# HealthMonitor.net
KiCad netlist of a schematic drawn in EAGLE
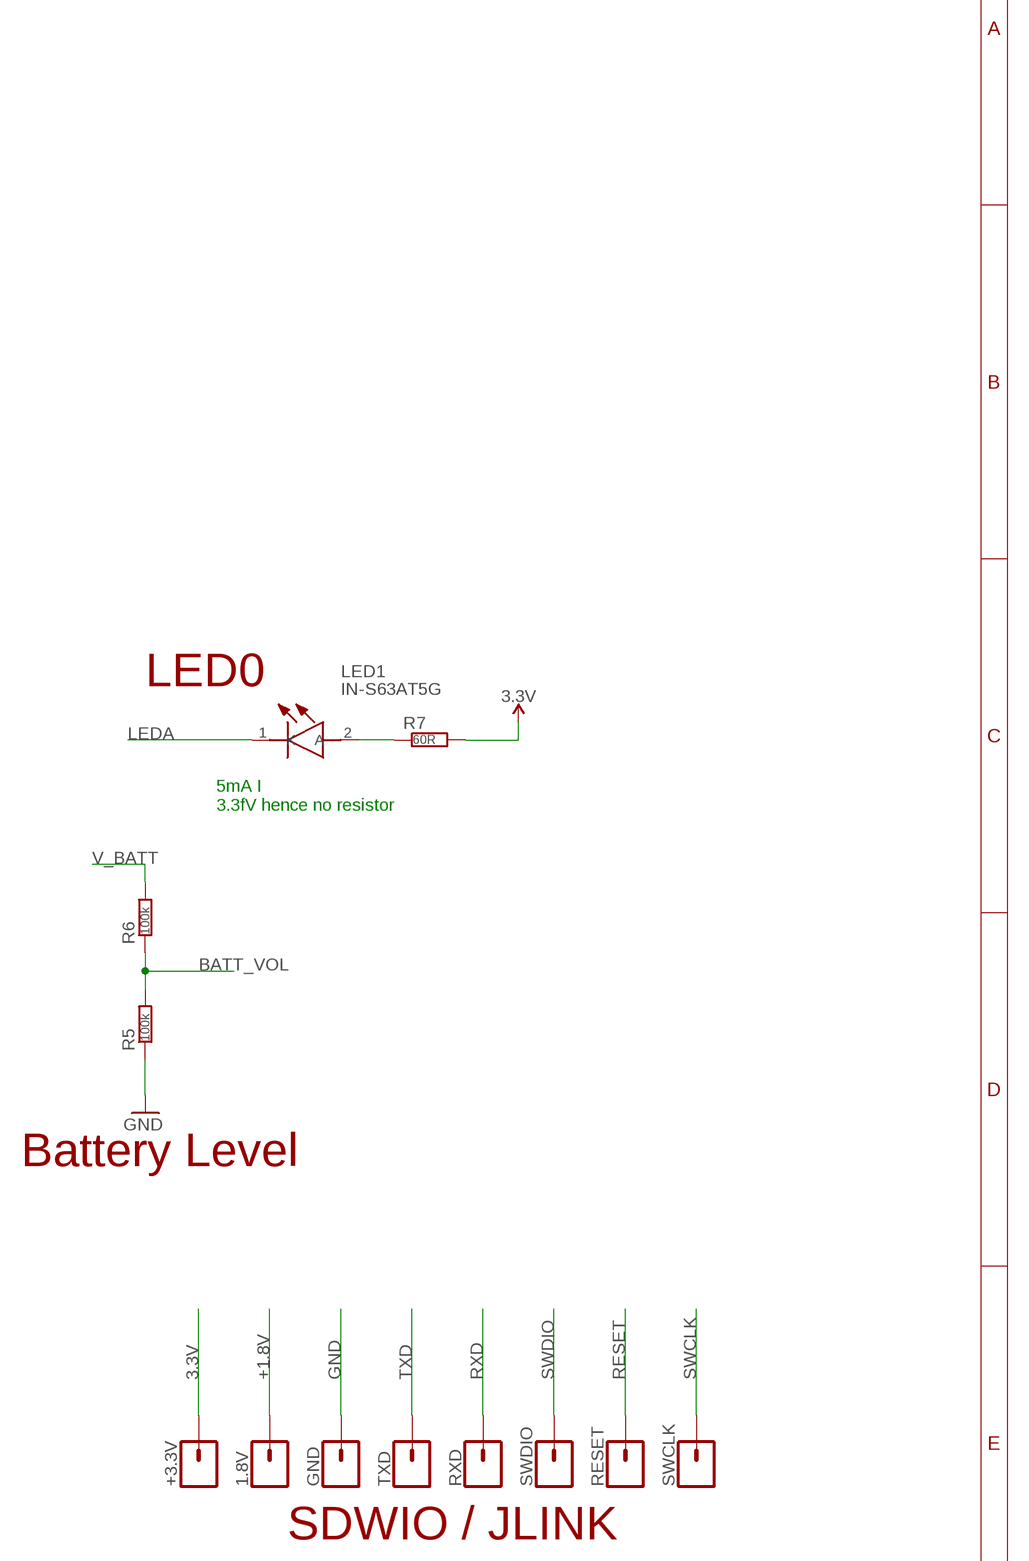
[diagram p0: schematic, sheet 1, part 1 of 2]
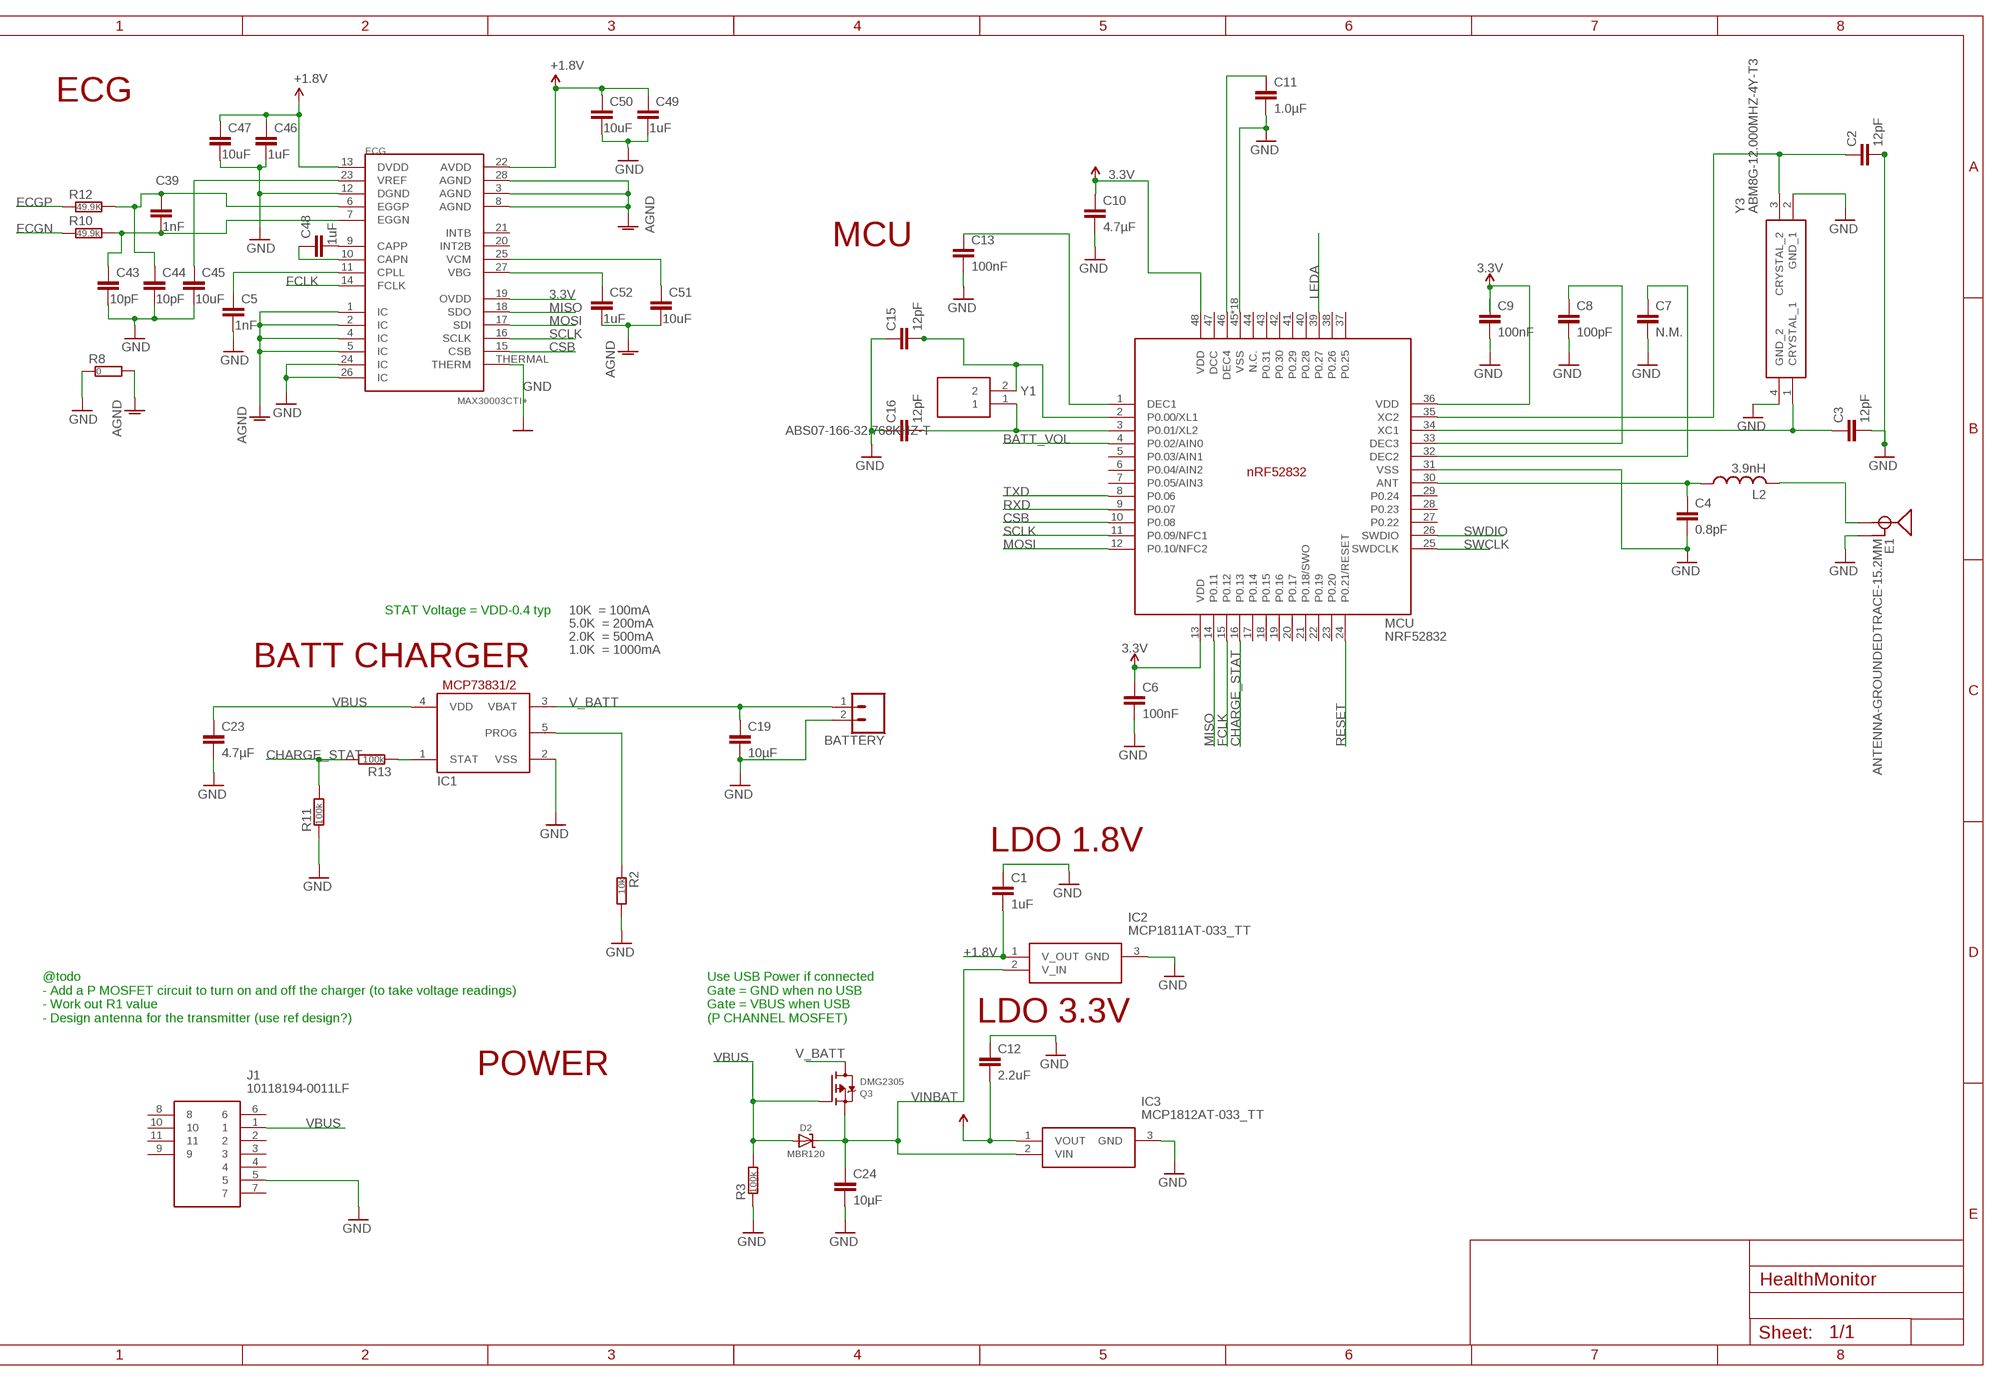
[diagram p1: schematic, sheet 1, part 2 of 2]

(export (version "E")
  (design (tool "Eeschema 10.0.6"))
  (components
    (comp (ref "+3.3V")
      (value "CONN_01")
      (footprint "eagle-import:1X01")
      (libsource (lib "eagle-import") (part "CONN_01"))
    )
    (comp (ref "1.8V")
      (value "CONN_01")
      (footprint "eagle-import:1X01")
      (libsource (lib "eagle-import") (part "CONN_01"))
    )
    (comp (ref "BATTERY")
      (value "CONN_02")
      (footprint "eagle-import:1X02")
      (libsource (lib "eagle-import") (part "CONN_02"))
    )
    (comp (ref "C1")
      (value "1uF")
      (footprint "eagle-import:RESC0603_N")
      (libsource (lib "eagle-import") (part "CAPACITOR_0603_N"))
    )
    (comp (ref "C2")
      (value "12pF")
      (footprint "eagle-import:RESC0603_N")
      (libsource (lib "eagle-import") (part "CAPACITOR_0603_N"))
    )
    (comp (ref "C3")
      (value "12pF")
      (footprint "eagle-import:RESC0603_N")
      (libsource (lib "eagle-import") (part "CAPACITOR_0603_N"))
    )
    (comp (ref "C4")
      (value "0.8pF")
      (footprint "eagle-import:RESC0603_N")
      (libsource (lib "eagle-import") (part "CAPACITOR_0603_N"))
    )
    (comp (ref "C5")
      (value "1nF")
      (footprint "eagle-import:RESC0603_N")
      (libsource (lib "eagle-import") (part "CAPACITOR_0603_N"))
    )
    (comp (ref "C6")
      (value "100nF")
      (footprint "eagle-import:RESC0603_N")
      (libsource (lib "eagle-import") (part "CAPACITOR_0603_N"))
    )
    (comp (ref "C7")
      (value "N.M.")
      (footprint "eagle-import:RESC0603_N")
      (libsource (lib "eagle-import") (part "CAPACITOR_0603_N"))
    )
    (comp (ref "C8")
      (value "100pF")
      (footprint "eagle-import:RESC0603_N")
      (libsource (lib "eagle-import") (part "CAPACITOR_0603_N"))
    )
    (comp (ref "C9")
      (value "100nF")
      (footprint "eagle-import:RESC0603_N")
      (libsource (lib "eagle-import") (part "CAPACITOR_0603_N"))
    )
    (comp (ref "C10")
      (value "4.7µF")
      (footprint "eagle-import:RESC0603_N")
      (libsource (lib "eagle-import") (part "CAPACITOR_0603_N"))
    )
    (comp (ref "C11")
      (value "1.0µF")
      (footprint "eagle-import:RESC0603_N")
      (libsource (lib "eagle-import") (part "CAPACITOR_0603_N"))
    )
    (comp (ref "C12")
      (value "2.2uF")
      (footprint "eagle-import:RESC0603_N")
      (libsource (lib "eagle-import") (part "CAPACITOR_0603_N"))
    )
    (comp (ref "C13")
      (value "100nF")
      (footprint "eagle-import:RESC0603_N")
      (libsource (lib "eagle-import") (part "CAPACITOR_0603_N"))
    )
    (comp (ref "C15")
      (value "12pF")
      (footprint "eagle-import:RESC0603_N")
      (libsource (lib "eagle-import") (part "CAPACITOR_0603_N"))
    )
    (comp (ref "C16")
      (value "12pF")
      (footprint "eagle-import:RESC0603_N")
      (libsource (lib "eagle-import") (part "CAPACITOR_0603_N"))
    )
    (comp (ref "C19")
      (value "10µF")
      (footprint "eagle-import:RESC0603_N")
      (libsource (lib "eagle-import") (part "CAPACITOR_0603_N"))
    )
    (comp (ref "C23")
      (value "4.7µF")
      (footprint "eagle-import:RESC0603_N")
      (libsource (lib "eagle-import") (part "CAPACITOR_0603_N"))
    )
    (comp (ref "C24")
      (value "10µF")
      (footprint "eagle-import:RESC0603_N")
      (libsource (lib "eagle-import") (part "CAPACITOR_0603_N"))
    )
    (comp (ref "C39")
      (value "1nF")
      (footprint "eagle-import:RESC0603_N")
      (libsource (lib "eagle-import") (part "CAPACITOR_0603_N"))
    )
    (comp (ref "C43")
      (value "10pF")
      (footprint "eagle-import:RESC0603_N")
      (libsource (lib "eagle-import") (part "CAPACITOR_0603_N"))
    )
    (comp (ref "C44")
      (value "10pF")
      (footprint "eagle-import:RESC0603_N")
      (libsource (lib "eagle-import") (part "CAPACITOR_0603_N"))
    )
    (comp (ref "C45")
      (value "10uF")
      (footprint "eagle-import:RESC0603_N")
      (libsource (lib "eagle-import") (part "CAPACITOR_0603_N"))
    )
    (comp (ref "C46")
      (value "1uF")
      (footprint "eagle-import:RESC0603_N")
      (libsource (lib "eagle-import") (part "CAPACITOR_0603_N"))
    )
    (comp (ref "C47")
      (value "10uF")
      (footprint "eagle-import:RESC0603_N")
      (libsource (lib "eagle-import") (part "CAPACITOR_0603_N"))
    )
    (comp (ref "C48")
      (value "1uF")
      (footprint "eagle-import:RESC0603_N")
      (libsource (lib "eagle-import") (part "CAPACITOR_0603_N"))
    )
    (comp (ref "C49")
      (value "1uF")
      (footprint "eagle-import:RESC0603_N")
      (libsource (lib "eagle-import") (part "CAPACITOR_0603_N"))
    )
    (comp (ref "C50")
      (value "10uF")
      (footprint "eagle-import:RESC0603_N")
      (libsource (lib "eagle-import") (part "CAPACITOR_0603_N"))
    )
    (comp (ref "C51")
      (value "10uF")
      (footprint "eagle-import:RESC0603_N")
      (libsource (lib "eagle-import") (part "CAPACITOR_0603_N"))
    )
    (comp (ref "C52")
      (value "1uF")
      (footprint "eagle-import:RESC0603_N")
      (libsource (lib "eagle-import") (part "CAPACITOR_0603_N"))
    )
    (comp (ref "D2")
      (value "MBR120")
      (footprint "eagle-import:SOD-123")
      (libsource (lib "eagle-import") (part "DIODE-SCHOTTKYSOD-123"))
    )
    (comp (ref "E1")
      (value "ANTENNA-GROUNDEDTRACE-15.2MM")
      (footprint "eagle-import:TRACE_ANTENNA_2.4GHZ_15.2MM")
      (libsource (lib "eagle-import") (part "ANTENNA-GROUNDEDTRACE-15.2MM"))
    )
    (comp (ref "ECG")
      (value "MAX30003CTI+")
      (footprint "eagle-import:QFN-28")
      (libsource (lib "eagle-import") (part "MAX30003"))
    )
    (comp (ref "GND")
      (value "CONN_01")
      (footprint "eagle-import:1X01")
      (libsource (lib "eagle-import") (part "CONN_01"))
    )
    (comp (ref "IC1")
      (value "MCP73831/OT")
      (footprint "eagle-import:SOT23-5L")
      (libsource (lib "eagle-import") (part "MCP73831/OT"))
    )
    (comp (ref "IC2")
      (value "MCP1811AT-033_TT")
      (footprint "eagle-import:SOT95P237X112-3N@1")
      (fields
        (field (name "MANUFACTURER_PART_NUMBER") "MCP1811AT-033/TT")
        (field (name "MOUSER_PART_NUMBER") "579-MCP1811AT-033/TT")
      )
      (libsource (lib "eagle-import") (part "MCP1811AT-033_TT"))
    )
    (comp (ref "IC3")
      (value "MCP1812AT-033_TT")
      (footprint "eagle-import:SOT95P237X112-3N")
      (fields
        (field (name "MANUFACTURER_PART_NUMBER") "MCP1812AT-033/TT")
        (field (name "MOUSER_PART_NUMBER") "579-MCP1812AT-033/TT")
      )
      (libsource (lib "eagle-import") (part "MCP1812AT-033_TT"))
    )
    (comp (ref "J1")
      (value "10118194-0011LF")
      (footprint "eagle-import:101181940011LF")
      (fields (field (name "MOUSER_PART_NUMBER") "649-10118194-0011LF"))
      (libsource (lib "eagle-import") (part "10118194-0011LF"))
    )
    (comp (ref "L2")
      (value "3.9nH")
      (footprint "eagle-import:RESC0603_N")
      (libsource (lib "eagle-import") (part "INDUCTOR_0603_N"))
    )
    (comp (ref "LED1")
      (value "IN-S63AT5G")
      (footprint "eagle-import:LEDM168X39N")
      (fields (field (name "MOUSER_PART_NUMBER") "743-IN-S63AT5G"))
      (libsource (lib "eagle-import") (part "IN-S63AT5G"))
    )
    (comp (ref "MCU")
      (value "NRF52832")
      (footprint "eagle-import:QFN40P600X600X90-48_N")
      (libsource (lib "eagle-import") (part "NRF52832"))
    )
    (comp (ref "Q3")
      (value "DMG2305")
      (footprint "eagle-import:SOT23-R")
      (libsource (lib "eagle-import") (part "MOSFET-P"))
    )
    (comp (ref "R2")
      (value "10k")
      (footprint "eagle-import:RESC0603_N")
      (libsource (lib "eagle-import") (part "RESISTOR_0603_N"))
    )
    (comp (ref "R3")
      (value "100k")
      (footprint "eagle-import:RESC0603_N")
      (libsource (lib "eagle-import") (part "RESISTOR_0603_N"))
    )
    (comp (ref "R5")
      (value "100k")
      (footprint "eagle-import:RESC0603_N")
      (libsource (lib "eagle-import") (part "RESISTOR_0603_N"))
    )
    (comp (ref "R6")
      (value "100k")
      (footprint "eagle-import:RESC0603_N")
      (libsource (lib "eagle-import") (part "RESISTOR_0603_N"))
    )
    (comp (ref "R7")
      (value "60R")
      (footprint "eagle-import:RESC0603_N")
      (libsource (lib "eagle-import") (part "RESISTOR_0603_N"))
    )
    (comp (ref "R8")
      (value "0")
      (footprint "eagle-import:RESC0603_N")
      (libsource (lib "eagle-import") (part "RESISTOR_0603_N"))
    )
    (comp (ref "R10")
      (value "49.9k")
      (footprint "eagle-import:RESC0603_N")
      (libsource (lib "eagle-import") (part "RESISTOR_0603_N"))
    )
    (comp (ref "R11")
      (value "100k")
      (footprint "eagle-import:RESC0603_N")
      (libsource (lib "eagle-import") (part "RESISTOR_0603_N"))
    )
    (comp (ref "R12")
      (value "49.9K")
      (footprint "eagle-import:RESC0603_N")
      (libsource (lib "eagle-import") (part "RESISTOR_0603_N"))
    )
    (comp (ref "R13")
      (value "100k")
      (footprint "eagle-import:RESC0603_N")
      (libsource (lib "eagle-import") (part "RESISTOR_0603_N"))
    )
    (comp (ref "RESET")
      (value "CONN_01")
      (footprint "eagle-import:1X01")
      (libsource (lib "eagle-import") (part "CONN_01"))
    )
    (comp (ref "RXD")
      (value "CONN_01")
      (footprint "eagle-import:1X01")
      (libsource (lib "eagle-import") (part "CONN_01"))
    )
    (comp (ref "SWCLK")
      (value "CONN_01")
      (footprint "eagle-import:1X01")
      (libsource (lib "eagle-import") (part "CONN_01"))
    )
    (comp (ref "SWDIO")
      (value "CONN_01")
      (footprint "eagle-import:1X01")
      (libsource (lib "eagle-import") (part "CONN_01"))
    )
    (comp (ref "TXD")
      (value "CONN_01")
      (footprint "eagle-import:1X01")
      (libsource (lib "eagle-import") (part "CONN_01"))
    )
    (comp (ref "Y1")
      (value "ABS07-166-32.768KHZ-T")
      (footprint "eagle-import:ABS0716632768KHZT")
      (fields
        (field (name "MOUSER_PART_NUMBER") "815-ABS0716632.768KT")
        (field (name "RS_PART_NUMBER") "1753474P")
      )
      (libsource (lib "eagle-import") (part "ABS07-166-32.768KHZ-T"))
    )
    (comp (ref "Y3")
      (value "ABM8G-12.000MHZ-4Y-T3")
      (footprint "eagle-import:ABM8G16000MHZB4YT")
      (fields
        (field (name "MOUSER_PART_NUMBER") "815-ABM8G-12-4YT3")
        (field (name "RS_PART_NUMBER") "1712832P")
      )
      (libsource (lib "eagle-import") (part "ABM8G-12.000MHZ-4Y-T3"))
    )
  )
  (nets
    (net (code "1") (name "+1.8V") (class "Default")
      (node (ref "1.8V") (pin "1") (pinfunction "1_1") (pintype "passive"))
      (node (ref "C1") (pin "2") (pinfunction "2_2") (pintype "passive"))
      (node (ref "C46") (pin "1") (pinfunction "1_1") (pintype "passive"))
      (node (ref "C47") (pin "1") (pinfunction "1_1") (pintype "passive"))
      (node (ref "C49") (pin "1") (pinfunction "1_1") (pintype "passive"))
      (node (ref "C50") (pin "1") (pinfunction "1_1") (pintype "passive"))
      (node (ref "ECG") (pin "13") (pinfunction "DVDD_13") (pintype "bidirectional"))
      (node (ref "ECG") (pin "22") (pinfunction "AVDD_22") (pintype "bidirectional"))
      (node (ref "IC2") (pin "1") (pinfunction "V_OUT_1") (pintype "bidirectional"))
    )
    (net (code "2") (name "/BATT_VOL") (class "Default")
      (node (ref "MCU") (pin "4") (pinfunction "P0.02/AIN0_4") (pintype "bidirectional"))
      (node (ref "R5") (pin "2") (pinfunction "2_2") (pintype "passive"))
      (node (ref "R6") (pin "1") (pinfunction "1_1") (pintype "passive"))
    )
    (net (code "3") (name "/CHARGE_STAT") (class "Default")
      (node (ref "MCU") (pin "16") (pinfunction "P0.13_16") (pintype "bidirectional"))
      (node (ref "R11") (pin "2") (pinfunction "2_2") (pintype "passive"))
      (node (ref "R13") (pin "2") (pinfunction "2_2") (pintype "passive"))
    )
    (net (code "4") (name "/CSB") (class "Default")
      (node (ref "ECG") (pin "15") (pinfunction "CSB_15") (pintype "bidirectional"))
      (node (ref "MCU") (pin "10") (pinfunction "P0.08_10") (pintype "bidirectional"))
    )
    (net (code "5") (name "/ECGN") (class "Default")
      (node (ref "R10") (pin "1") (pinfunction "1_1") (pintype "passive"))
    )
    (net (code "6") (name "/ECGP") (class "Default")
      (node (ref "R12") (pin "1") (pinfunction "1_1") (pintype "passive"))
    )
    (net (code "7") (name "/FCLK") (class "Default")
      (node (ref "ECG") (pin "14") (pinfunction "FCLK_14") (pintype "bidirectional"))
      (node (ref "MCU") (pin "15") (pinfunction "P0.12_15") (pintype "bidirectional"))
    )
    (net (code "8") (name "/LEDA") (class "Default")
      (node (ref "LED1") (pin "1") (pinfunction "K_1") (pintype "bidirectional"))
      (node (ref "MCU") (pin "39") (pinfunction "P0.27_39") (pintype "bidirectional"))
    )
    (net (code "9") (name "/MISO") (class "Default")
      (node (ref "ECG") (pin "18") (pinfunction "SDO_18") (pintype "bidirectional"))
      (node (ref "MCU") (pin "14") (pinfunction "P0.11_14") (pintype "bidirectional"))
    )
    (net (code "10") (name "/MOSI") (class "Default")
      (node (ref "ECG") (pin "17") (pinfunction "SDI_17") (pintype "bidirectional"))
      (node (ref "MCU") (pin "12") (pinfunction "P0.10/NFC2_12") (pintype "bidirectional"))
    )
    (net (code "11") (name "/RESET") (class "Default")
      (node (ref "MCU") (pin "24") (pinfunction "P0.21/RESET_24") (pintype "bidirectional"))
      (node (ref "RESET") (pin "1") (pinfunction "1_1") (pintype "passive"))
    )
    (net (code "12") (name "/RXD") (class "Default")
      (node (ref "MCU") (pin "9") (pinfunction "P0.07_9") (pintype "bidirectional"))
      (node (ref "RXD") (pin "1") (pinfunction "1_1") (pintype "passive"))
    )
    (net (code "13") (name "/SCLK") (class "Default")
      (node (ref "ECG") (pin "16") (pinfunction "SCLK_16") (pintype "bidirectional"))
      (node (ref "MCU") (pin "11") (pinfunction "P0.09/NFC1_11") (pintype "bidirectional"))
    )
    (net (code "14") (name "/SWCLK") (class "Default")
      (node (ref "MCU") (pin "25") (pinfunction "SWDCLK_25") (pintype "input"))
      (node (ref "SWCLK") (pin "1") (pinfunction "1_1") (pintype "passive"))
    )
    (net (code "15") (name "/SWDIO") (class "Default")
      (node (ref "MCU") (pin "26") (pinfunction "SWDIO_26") (pintype "bidirectional"))
      (node (ref "SWDIO") (pin "1") (pinfunction "1_1") (pintype "passive"))
    )
    (net (code "16") (name "/TXD") (class "Default")
      (node (ref "MCU") (pin "8") (pinfunction "P0.06_8") (pintype "bidirectional"))
      (node (ref "TXD") (pin "1") (pinfunction "1_1") (pintype "passive"))
    )
    (net (code "17") (name "/VBUS") (class "Default")
      (node (ref "C23") (pin "1") (pinfunction "1_1") (pintype "passive"))
      (node (ref "D2") (pin "A") (pinfunction "A_A") (pintype "passive"))
      (node (ref "IC1") (pin "4") (pinfunction "VDD_4") (pintype "power_in"))
      (node (ref "J1") (pin "1") (pinfunction "1_1") (pintype "bidirectional"))
      (node (ref "Q3") (pin "1") (pinfunction "G_1") (pintype "passive"))
      (node (ref "R3") (pin "2") (pinfunction "2_2") (pintype "passive"))
    )
    (net (code "18") (name "/VINBAT") (class "Default")
      (node (ref "C24") (pin "1") (pinfunction "1_1") (pintype "passive"))
      (node (ref "D2") (pin "C") (pinfunction "C_C") (pintype "passive"))
      (node (ref "IC2") (pin "2") (pinfunction "V_IN_2") (pintype "bidirectional"))
      (node (ref "IC3") (pin "2") (pinfunction "VIN_2") (pintype "bidirectional"))
      (node (ref "Q3") (pin "2") (pinfunction "S_2") (pintype "passive"))
    )
    (net (code "19") (name "/V_BATT") (class "Default")
      (node (ref "BATTERY") (pin "1") (pinfunction "1_1") (pintype "passive"))
      (node (ref "C19") (pin "1") (pinfunction "1_1") (pintype "passive"))
      (node (ref "IC1") (pin "3") (pinfunction "VBAT_3") (pintype "bidirectional"))
      (node (ref "Q3") (pin "3") (pinfunction "D_3") (pintype "passive"))
      (node (ref "R6") (pin "2") (pinfunction "2_2") (pintype "passive"))
    )
    (net (code "20") (name "3.3V") (class "Default")
      (node (ref "+3.3V") (pin "1") (pinfunction "1_1") (pintype "passive"))
      (node (ref "C10") (pin "1") (pinfunction "1_1") (pintype "passive"))
      (node (ref "C12") (pin "2") (pinfunction "2_2") (pintype "passive"))
      (node (ref "C6") (pin "1") (pinfunction "1_1") (pintype "passive"))
      (node (ref "C9") (pin "1") (pinfunction "1_1") (pintype "passive"))
      (node (ref "ECG") (pin "19") (pinfunction "OVDD_19") (pintype "bidirectional"))
      (node (ref "IC3") (pin "1") (pinfunction "VOUT_1") (pintype "bidirectional"))
      (node (ref "MCU") (pin "13") (pinfunction "VDD_13") (pintype "power_in"))
      (node (ref "MCU") (pin "36") (pinfunction "VDD_36") (pintype "power_in"))
      (node (ref "MCU") (pin "48") (pinfunction "VDD_48") (pintype "power_in"))
      (node (ref "R7") (pin "2") (pinfunction "2_2") (pintype "passive"))
    )
    (net (code "21") (name "AGND") (class "Default")
      (node (ref "C51") (pin "2") (pinfunction "2_2") (pintype "passive"))
      (node (ref "C52") (pin "2") (pinfunction "2_2") (pintype "passive"))
      (node (ref "ECG") (pin "1") (pinfunction "IC_1") (pintype "bidirectional"))
      (node (ref "ECG") (pin "2") (pinfunction "IC_2") (pintype "bidirectional"))
      (node (ref "ECG") (pin "28") (pinfunction "AGND_28") (pintype "bidirectional"))
      (node (ref "ECG") (pin "3") (pinfunction "AGND_3") (pintype "bidirectional"))
      (node (ref "ECG") (pin "4") (pinfunction "IC_4") (pintype "bidirectional"))
      (node (ref "ECG") (pin "5") (pinfunction "IC_5") (pintype "bidirectional"))
      (node (ref "ECG") (pin "8") (pinfunction "AGND_8") (pintype "bidirectional"))
      (node (ref "R8") (pin "2") (pinfunction "2_2") (pintype "passive"))
    )
    (net (code "22") (name "GND") (class "Default")
      (node (ref "BATTERY") (pin "2") (pinfunction "2_2") (pintype "passive"))
      (node (ref "C1") (pin "1") (pinfunction "1_1") (pintype "passive"))
      (node (ref "C10") (pin "2") (pinfunction "2_2") (pintype "passive"))
      (node (ref "C11") (pin "2") (pinfunction "2_2") (pintype "passive"))
      (node (ref "C12") (pin "1") (pinfunction "1_1") (pintype "passive"))
      (node (ref "C13") (pin "2") (pinfunction "2_2") (pintype "passive"))
      (node (ref "C15") (pin "1") (pinfunction "1_1") (pintype "passive"))
      (node (ref "C16") (pin "1") (pinfunction "1_1") (pintype "passive"))
      (node (ref "C19") (pin "2") (pinfunction "2_2") (pintype "passive"))
      (node (ref "C2") (pin "2") (pinfunction "2_2") (pintype "passive"))
      (node (ref "C23") (pin "2") (pinfunction "2_2") (pintype "passive"))
      (node (ref "C24") (pin "2") (pinfunction "2_2") (pintype "passive"))
      (node (ref "C3") (pin "2") (pinfunction "2_2") (pintype "passive"))
      (node (ref "C4") (pin "2") (pinfunction "2_2") (pintype "passive"))
      (node (ref "C43") (pin "2") (pinfunction "2_2") (pintype "passive"))
      (node (ref "C44") (pin "2") (pinfunction "2_2") (pintype "passive"))
      (node (ref "C45") (pin "2") (pinfunction "2_2") (pintype "passive"))
      (node (ref "C46") (pin "2") (pinfunction "2_2") (pintype "passive"))
      (node (ref "C47") (pin "2") (pinfunction "2_2") (pintype "passive"))
      (node (ref "C49") (pin "2") (pinfunction "2_2") (pintype "passive"))
      (node (ref "C5") (pin "2") (pinfunction "2_2") (pintype "passive"))
      (node (ref "C50") (pin "2") (pinfunction "2_2") (pintype "passive"))
      (node (ref "C6") (pin "2") (pinfunction "2_2") (pintype "passive"))
      (node (ref "C7") (pin "2") (pinfunction "2_2") (pintype "passive"))
      (node (ref "C8") (pin "2") (pinfunction "2_2") (pintype "passive"))
      (node (ref "C9") (pin "2") (pinfunction "2_2") (pintype "passive"))
      (node (ref "E1") (pin "GND") (pinfunction "GND_GND") (pintype "bidirectional"))
      (node (ref "ECG") (pin "12") (pinfunction "DGND_12") (pintype "bidirectional"))
      (node (ref "ECG") (pin "24") (pinfunction "IC_24") (pintype "bidirectional"))
      (node (ref "ECG") (pin "26") (pinfunction "IC_26") (pintype "bidirectional"))
      (node (ref "ECG") (pin "THERMAL") (pinfunction "THERM_THERMAL") (pintype "bidirectional"))
      (node (ref "GND") (pin "1") (pinfunction "1_1") (pintype "passive"))
      (node (ref "IC1") (pin "2") (pinfunction "VSS_2") (pintype "power_in"))
      (node (ref "IC2") (pin "3") (pinfunction "GND_3") (pintype "bidirectional"))
      (node (ref "IC3") (pin "3") (pinfunction "GND_3") (pintype "bidirectional"))
      (node (ref "J1") (pin "5") (pinfunction "5_5") (pintype "bidirectional"))
      (node (ref "MCU") (pin "31") (pinfunction "VSS_31") (pintype "bidirectional"))
      (node (ref "MCU") (pin "45") (pinfunction "VSS_45") (pintype "power_in"))
      (node (ref "MCU") (pin "PAD") (pinfunction "VSS_PAD") (pintype "power_in"))
      (node (ref "MCU") (pin "PAD@VIA01") (pinfunction "VSS_PAD@VIA01") (pintype "power_in"))
      (node (ref "MCU") (pin "PAD@VIA02") (pinfunction "VSS_PAD@VIA02") (pintype "power_in"))
      (node (ref "MCU") (pin "PAD@VIA03") (pinfunction "VSS_PAD@VIA03") (pintype "power_in"))
      (node (ref "MCU") (pin "PAD@VIA04") (pinfunction "VSS_PAD@VIA04") (pintype "power_in"))
      (node (ref "MCU") (pin "PAD@VIA05") (pinfunction "VSS_PAD@VIA05") (pintype "power_in"))
      (node (ref "MCU") (pin "PAD@VIA06") (pinfunction "VSS_PAD@VIA06") (pintype "power_in"))
      (node (ref "MCU") (pin "PAD@VIA07") (pinfunction "VSS_PAD@VIA07") (pintype "power_in"))
      (node (ref "MCU") (pin "PAD@VIA08") (pinfunction "VSS_PAD@VIA08") (pintype "power_in"))
      (node (ref "MCU") (pin "PAD@VIA09") (pinfunction "VSS_PAD@VIA09") (pintype "power_in"))
      (node (ref "MCU") (pin "PAD@VIA10") (pinfunction "VSS_PAD@VIA10") (pintype "power_in"))
      (node (ref "MCU") (pin "PAD@VIA11") (pinfunction "VSS_PAD@VIA11") (pintype "power_in"))
      (node (ref "MCU") (pin "PAD@VIA12") (pinfunction "VSS_PAD@VIA12") (pintype "power_in"))
      (node (ref "MCU") (pin "PAD@VIA13") (pinfunction "VSS_PAD@VIA13") (pintype "power_in"))
      (node (ref "MCU") (pin "PAD@VIA14") (pinfunction "VSS_PAD@VIA14") (pintype "power_in"))
      (node (ref "MCU") (pin "PAD@VIA15") (pinfunction "VSS_PAD@VIA15") (pintype "power_in"))
      (node (ref "MCU") (pin "PAD@VIA16") (pinfunction "VSS_PAD@VIA16") (pintype "power_in"))
      (node (ref "R11") (pin "1") (pinfunction "1_1") (pintype "passive"))
      (node (ref "R2") (pin "2") (pinfunction "2_2") (pintype "passive"))
      (node (ref "R3") (pin "1") (pinfunction "1_1") (pintype "passive"))
      (node (ref "R5") (pin "1") (pinfunction "1_1") (pintype "passive"))
      (node (ref "R8") (pin "1") (pinfunction "1_1") (pintype "passive"))
      (node (ref "Y3") (pin "2") (pinfunction "GND_1_2") (pintype "bidirectional"))
      (node (ref "Y3") (pin "4") (pinfunction "GND_2_4") (pintype "bidirectional"))
    )
    (net (code "23") (name "Net-(E1-SIGNAL)") (class "Default")
      (node (ref "E1") (pin "ANT") (pinfunction "SIGNAL_ANT") (pintype "bidirectional"))
      (node (ref "L2") (pin "2") (pinfunction "2_2") (pintype "passive"))
    )
    (net (code "24") (name "Net-(ECG-CAPN)") (class "Default")
      (node (ref "C48") (pin "1") (pinfunction "1_1") (pintype "passive"))
      (node (ref "ECG") (pin "10") (pinfunction "CAPN_10") (pintype "bidirectional"))
    )
    (net (code "25") (name "Net-(ECG-CAPP)") (class "Default")
      (node (ref "C48") (pin "2") (pinfunction "2_2") (pintype "passive"))
      (node (ref "ECG") (pin "9") (pinfunction "CAPP_9") (pintype "bidirectional"))
    )
    (net (code "26") (name "Net-(ECG-CPLL)") (class "Default")
      (node (ref "C5") (pin "1") (pinfunction "1_1") (pintype "passive"))
      (node (ref "ECG") (pin "11") (pinfunction "CPLL_11") (pintype "bidirectional"))
    )
    (net (code "27") (name "Net-(ECG-EGGN)") (class "Default")
      (node (ref "C39") (pin "2") (pinfunction "2_2") (pintype "passive"))
      (node (ref "C43") (pin "1") (pinfunction "1_1") (pintype "passive"))
      (node (ref "ECG") (pin "7") (pinfunction "EGGN_7") (pintype "bidirectional"))
      (node (ref "R10") (pin "2") (pinfunction "2_2") (pintype "passive"))
    )
    (net (code "28") (name "Net-(ECG-EGGP)") (class "Default")
      (node (ref "C39") (pin "1") (pinfunction "1_1") (pintype "passive"))
      (node (ref "C44") (pin "1") (pinfunction "1_1") (pintype "passive"))
      (node (ref "ECG") (pin "6") (pinfunction "EGGP_6") (pintype "bidirectional"))
      (node (ref "R12") (pin "2") (pinfunction "2_2") (pintype "passive"))
    )
    (net (code "29") (name "Net-(ECG-VBG)") (class "Default")
      (node (ref "C52") (pin "1") (pinfunction "1_1") (pintype "passive"))
      (node (ref "ECG") (pin "27") (pinfunction "VBG_27") (pintype "bidirectional"))
    )
    (net (code "30") (name "Net-(ECG-VCM)") (class "Default")
      (node (ref "C51") (pin "1") (pinfunction "1_1") (pintype "passive"))
      (node (ref "ECG") (pin "25") (pinfunction "VCM_25") (pintype "bidirectional"))
    )
    (net (code "31") (name "Net-(ECG-VREF)") (class "Default")
      (node (ref "C45") (pin "1") (pinfunction "1_1") (pintype "passive"))
      (node (ref "ECG") (pin "23") (pinfunction "VREF_23") (pintype "bidirectional"))
    )
    (net (code "32") (name "Net-(IC1-PROG)") (class "Default")
      (node (ref "IC1") (pin "5") (pinfunction "PROG_5") (pintype "input"))
      (node (ref "R2") (pin "1") (pinfunction "1_1") (pintype "passive"))
    )
    (net (code "33") (name "Net-(IC1-STAT)") (class "Default")
      (node (ref "IC1") (pin "1") (pinfunction "STAT_1") (pintype "output"))
      (node (ref "R13") (pin "1") (pinfunction "1_1") (pintype "passive"))
    )
    (net (code "34") (name "Net-(LED1-A)") (class "Default")
      (node (ref "LED1") (pin "2") (pinfunction "A_2") (pintype "bidirectional"))
      (node (ref "R7") (pin "1") (pinfunction "1_1") (pintype "passive"))
    )
    (net (code "35") (name "Net-(MCU-ANT)") (class "Default")
      (node (ref "C4") (pin "1") (pinfunction "1_1") (pintype "passive"))
      (node (ref "L2") (pin "1") (pinfunction "1_1") (pintype "passive"))
      (node (ref "MCU") (pin "30") (pinfunction "ANT_30") (pintype "bidirectional"))
    )
    (net (code "36") (name "Net-(MCU-DEC1)") (class "Default")
      (node (ref "C13") (pin "1") (pinfunction "1_1") (pintype "passive"))
      (node (ref "MCU") (pin "1") (pinfunction "DEC1_1") (pintype "power_in"))
    )
    (net (code "37") (name "Net-(MCU-DEC2)") (class "Default")
      (node (ref "C7") (pin "1") (pinfunction "1_1") (pintype "passive"))
      (node (ref "MCU") (pin "32") (pinfunction "DEC2_32") (pintype "bidirectional"))
    )
    (net (code "38") (name "Net-(MCU-DEC3)") (class "Default")
      (node (ref "C8") (pin "1") (pinfunction "1_1") (pintype "passive"))
      (node (ref "MCU") (pin "33") (pinfunction "DEC3_33") (pintype "bidirectional"))
    )
    (net (code "39") (name "Net-(MCU-DEC4)") (class "Default")
      (node (ref "C11") (pin "1") (pinfunction "1_1") (pintype "passive"))
      (node (ref "MCU") (pin "46") (pinfunction "DEC4_46") (pintype "power_in"))
    )
    (net (code "40") (name "Net-(MCU-P0.00{slash}XL1)") (class "Default")
      (node (ref "C15") (pin "2") (pinfunction "2_2") (pintype "passive"))
      (node (ref "MCU") (pin "2") (pinfunction "P0.00/XL1_2") (pintype "bidirectional"))
      (node (ref "Y1") (pin "2") (pinfunction "2_2") (pintype "bidirectional"))
    )
    (net (code "41") (name "Net-(MCU-P0.01{slash}XL2)") (class "Default")
      (node (ref "C16") (pin "2") (pinfunction "2_2") (pintype "passive"))
      (node (ref "MCU") (pin "3") (pinfunction "P0.01/XL2_3") (pintype "bidirectional"))
      (node (ref "Y1") (pin "1") (pinfunction "1_1") (pintype "bidirectional"))
    )
    (net (code "42") (name "Net-(MCU-XC1)") (class "Default")
      (node (ref "C3") (pin "1") (pinfunction "1_1") (pintype "passive"))
      (node (ref "MCU") (pin "34") (pinfunction "XC1_34") (pintype "input"))
      (node (ref "Y3") (pin "1") (pinfunction "CRYSTAL_1_1") (pintype "bidirectional"))
    )
    (net (code "43") (name "Net-(MCU-XC2)") (class "Default")
      (node (ref "C2") (pin "1") (pinfunction "1_1") (pintype "passive"))
      (node (ref "MCU") (pin "35") (pinfunction "XC2_35") (pintype "output"))
      (node (ref "Y3") (pin "3") (pinfunction "CRYSTAL_2_3") (pintype "bidirectional"))
    )
    (net (code "44") (name "unconnected-(ECG-INT2B-Pad20)") (class "Default")
      (node (ref "ECG") (pin "20") (pinfunction "INT2B_20") (pintype "bidirectional"))
    )
    (net (code "45") (name "unconnected-(ECG-INTB-Pad21)") (class "Default")
      (node (ref "ECG") (pin "21") (pinfunction "INTB_21") (pintype "bidirectional"))
    )
    (net (code "46") (name "unconnected-(J1-Pad2)") (class "Default")
      (node (ref "J1") (pin "2") (pinfunction "2_2") (pintype "bidirectional"))
    )
    (net (code "47") (name "unconnected-(J1-Pad3)") (class "Default")
      (node (ref "J1") (pin "3") (pinfunction "3_3") (pintype "bidirectional"))
    )
    (net (code "48") (name "unconnected-(J1-Pad4)") (class "Default")
      (node (ref "J1") (pin "4") (pinfunction "4_4") (pintype "bidirectional"))
    )
    (net (code "49") (name "unconnected-(J1-Pad6)") (class "Default")
      (node (ref "J1") (pin "6") (pinfunction "6_6") (pintype "bidirectional"))
    )
    (net (code "50") (name "unconnected-(J1-Pad7)") (class "Default")
      (node (ref "J1") (pin "7") (pinfunction "7_7") (pintype "bidirectional"))
    )
    (net (code "51") (name "unconnected-(J1-Pad8)") (class "Default")
      (node (ref "J1") (pin "8") (pinfunction "8_8") (pintype "bidirectional"))
    )
    (net (code "52") (name "unconnected-(J1-Pad9)") (class "Default")
      (node (ref "J1") (pin "9") (pinfunction "9_9") (pintype "bidirectional"))
    )
    (net (code "53") (name "unconnected-(J1-Pad10)") (class "Default")
      (node (ref "J1") (pin "10") (pinfunction "10_10") (pintype "bidirectional"))
    )
    (net (code "54") (name "unconnected-(J1-Pad11)") (class "Default")
      (node (ref "J1") (pin "11") (pinfunction "11_11") (pintype "bidirectional"))
    )
    (net (code "55") (name "unconnected-(MCU-DCC-Pad47)") (class "Default")
      (node (ref "MCU") (pin "47") (pinfunction "DCC_47") (pintype "output"))
    )
    (net (code "56") (name "unconnected-(MCU-N.C.-Pad44)") (class "Default")
      (node (ref "MCU") (pin "44") (pinfunction "N.C._44") (pintype "no_connect"))
    )
    (net (code "57") (name "unconnected-(MCU-P0.03{slash}AIN1-Pad5)") (class "Default")
      (node (ref "MCU") (pin "5") (pinfunction "P0.03/AIN1_5") (pintype "bidirectional"))
    )
    (net (code "58") (name "unconnected-(MCU-P0.04{slash}AIN2-Pad6)") (class "Default")
      (node (ref "MCU") (pin "6") (pinfunction "P0.04/AIN2_6") (pintype "bidirectional"))
    )
    (net (code "59") (name "unconnected-(MCU-P0.05{slash}AIN3-Pad7)") (class "Default")
      (node (ref "MCU") (pin "7") (pinfunction "P0.05/AIN3_7") (pintype "bidirectional"))
    )
    (net (code "60") (name "unconnected-(MCU-P0.14-Pad17)") (class "Default")
      (node (ref "MCU") (pin "17") (pinfunction "P0.14_17") (pintype "bidirectional"))
    )
    (net (code "61") (name "unconnected-(MCU-P0.15-Pad18)") (class "Default")
      (node (ref "MCU") (pin "18") (pinfunction "P0.15_18") (pintype "bidirectional"))
    )
    (net (code "62") (name "unconnected-(MCU-P0.16-Pad19)") (class "Default")
      (node (ref "MCU") (pin "19") (pinfunction "P0.16_19") (pintype "bidirectional"))
    )
    (net (code "63") (name "unconnected-(MCU-P0.17-Pad20)") (class "Default")
      (node (ref "MCU") (pin "20") (pinfunction "P0.17_20") (pintype "bidirectional"))
    )
    (net (code "64") (name "unconnected-(MCU-P0.18{slash}SWO-Pad21)") (class "Default")
      (node (ref "MCU") (pin "21") (pinfunction "P0.18/SWO_21") (pintype "bidirectional"))
    )
    (net (code "65") (name "unconnected-(MCU-P0.19-Pad22)") (class "Default")
      (node (ref "MCU") (pin "22") (pinfunction "P0.19_22") (pintype "bidirectional"))
    )
    (net (code "66") (name "unconnected-(MCU-P0.20-Pad23)") (class "Default")
      (node (ref "MCU") (pin "23") (pinfunction "P0.20_23") (pintype "bidirectional"))
    )
    (net (code "67") (name "unconnected-(MCU-P0.22-Pad27)") (class "Default")
      (node (ref "MCU") (pin "27") (pinfunction "P0.22_27") (pintype "bidirectional"))
    )
    (net (code "68") (name "unconnected-(MCU-P0.23-Pad28)") (class "Default")
      (node (ref "MCU") (pin "28") (pinfunction "P0.23_28") (pintype "bidirectional"))
    )
    (net (code "69") (name "unconnected-(MCU-P0.24-Pad29)") (class "Default")
      (node (ref "MCU") (pin "29") (pinfunction "P0.24_29") (pintype "bidirectional"))
    )
    (net (code "70") (name "unconnected-(MCU-P0.25-Pad37)") (class "Default")
      (node (ref "MCU") (pin "37") (pinfunction "P0.25_37") (pintype "bidirectional"))
    )
    (net (code "71") (name "unconnected-(MCU-P0.26-Pad38)") (class "Default")
      (node (ref "MCU") (pin "38") (pinfunction "P0.26_38") (pintype "bidirectional"))
    )
    (net (code "72") (name "unconnected-(MCU-P0.28-Pad40)") (class "Default")
      (node (ref "MCU") (pin "40") (pinfunction "P0.28_40") (pintype "bidirectional"))
    )
    (net (code "73") (name "unconnected-(MCU-P0.29-Pad41)") (class "Default")
      (node (ref "MCU") (pin "41") (pinfunction "P0.29_41") (pintype "bidirectional"))
    )
    (net (code "74") (name "unconnected-(MCU-P0.30-Pad42)") (class "Default")
      (node (ref "MCU") (pin "42") (pinfunction "P0.30_42") (pintype "bidirectional"))
    )
    (net (code "75") (name "unconnected-(MCU-P0.31-Pad43)") (class "Default")
      (node (ref "MCU") (pin "43") (pinfunction "P0.31_43") (pintype "bidirectional"))
    )
  )
)
